# Control_Board.net
KiCad netlist of a schematic drawn in EAGLE
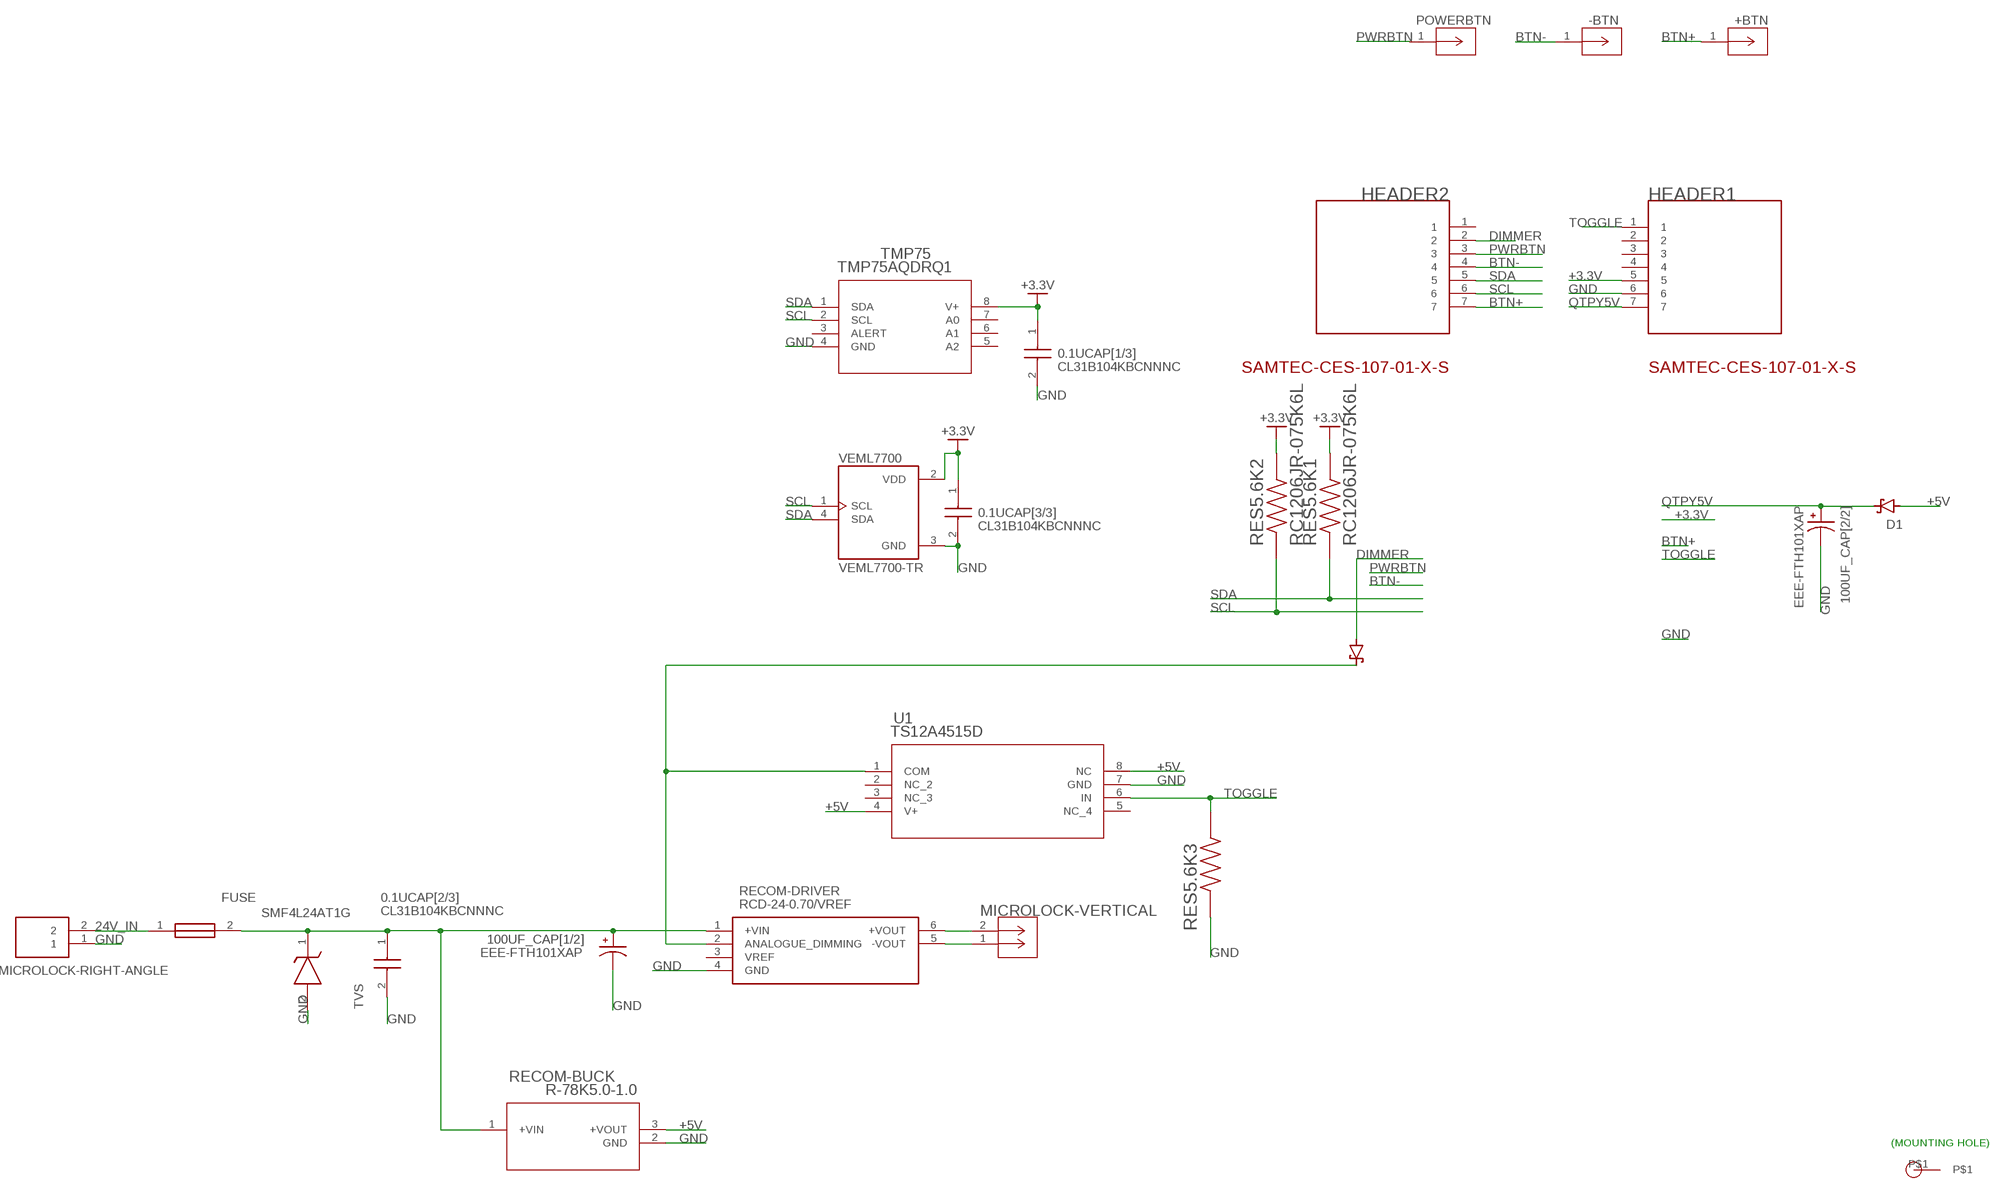
[diagram p0: schematic, sheet 1]

(export (version "E")
  (design (tool "Eeschema 10.0.6"))
  (components
    (comp (ref "+BTN")
      (value "807-22-001-10-001101")
      (footprint "eagle-import:CONN_807-22-001-10-001101_MIM")
      (fields (field (name "MANUFACTURER") "Mill-Max") (field (name "MPN") "807-22-001-10-001101"))
      (libsource (lib "eagle-import") (part "807-22-001-10-001101CONN_807-22-001-10-001101_MIM"))
    )
    (comp (ref "-BTN")
      (value "807-22-001-10-001101")
      (footprint "eagle-import:CONN_807-22-001-10-001101_MIM")
      (fields (field (name "MANUFACTURER") "Mill-Max") (field (name "MPN") "807-22-001-10-001101"))
      (libsource (lib "eagle-import") (part "807-22-001-10-001101CONN_807-22-001-10-001101_MIM"))
    )
    (comp (ref "0.1UCAP[1/3]")
      (value "CL31B104KBCNNNC")
      (footprint "eagle-import:CAPC3216X100N")
      (fields
        (field (name "MANUFACTURER") "Samsung Electro-Mechanics")
        (field (name "MPN") "CL31B104KBCNNNC")
      )
      (libsource (lib "eagle-import") (part "CL31B104KBCNNNC"))
    )
    (comp (ref "0.1UCAP[2/3]")
      (value "CL31B104KBCNNNC")
      (footprint "eagle-import:CAPC3216X100N")
      (fields
        (field (name "MANUFACTURER") "Samsung Electro-Mechanics")
        (field (name "MPN") "CL31B104KBCNNNC")
      )
      (libsource (lib "eagle-import") (part "CL31B104KBCNNNC"))
    )
    (comp (ref "0.1UCAP[3/3]")
      (value "CL31B104KBCNNNC")
      (footprint "eagle-import:CAPC3216X100N")
      (fields
        (field (name "MANUFACTURER") "Samsung Electro-Mechanics")
        (field (name "MPN") "CL31B104KBCNNNC")
      )
      (libsource (lib "eagle-import") (part "CL31B104KBCNNNC"))
    )
    (comp (ref "100UF_CAP[1/2]")
      (value "EEE-FTH101XAP")
      (footprint "eagle-import:CAP_EEEFTH101XAP")
      (fields (field (name "MANUFACTURER") "Panasonic") (field (name "MPN") "EEE-FTH101XAP"))
      (libsource (lib "eagle-import") (part "EEEFTH101XAP"))
    )
    (comp (ref "100UF_CAP[2/2]")
      (value "EEE-FTH101XAP")
      (footprint "eagle-import:CAP_EEEFTH101XAP")
      (fields (field (name "MANUFACTURER") "Panasonic") (field (name "MPN") "EEE-FTH101XAP"))
      (libsource (lib "eagle-import") (part "EEEFTH101XAP"))
    )
    (comp (ref "D1")
      (value "PMEG4010EGWX")
      (footprint "eagle-import:SOD-123")
      (fields (field (name "MANUFACTURER") "Nexperia") (field (name "MPN") "PMEG4010EGWX"))
      (libsource (lib "eagle-import") (part "PMEG4010EGWX"))
    )
    (comp (ref "D3")
      (value "PMEG4010EGWX")
      (footprint "eagle-import:SOD-123")
      (fields (field (name "MANUFACTURER") "Nexperia") (field (name "MPN") "PMEG4010EGWX"))
      (libsource (lib "eagle-import") (part "PMEG4010EGWX"))
    )
    (comp (ref "FUSE")
      (value "SMD2016B100TF/33")
      (footprint "eagle-import:SMD2016B100TF_33")
      (fields (field (name "MANUFACTURER") "YAGEO") (field (name "MPN") "SMD2016B100TF/33"))
      (libsource (lib "eagle-import") (part "SMD2016B100TF/33"))
    )
    (comp (ref "HEADER1")
      (value "CES-107-01-G-S")
      (footprint "eagle-import:SAMTEC-CES-107-01-X-S")
      (fields (field (name "MANUFACTURER") "Samtec"))
      (libsource (lib "eagle-import") (part "SAMTEC-CES-107-01-X-SJ"))
    )
    (comp (ref "HEADER2")
      (value "CES-107-01-G-S")
      (footprint "eagle-import:SAMTEC-CES-107-01-X-S")
      (fields (field (name "MANUFACTURER") "Samtec"))
      (libsource (lib "eagle-import") (part "SAMTEC-CES-107-01-X-SJ"))
    )
    (comp (ref "MICROLOCK-RIGHT-ANGLE")
      (value "2200980271")
      (footprint "eagle-import:2200980271")
      (fields (field (name "MANUFACTURER") "Molex") (field (name "MPN") "2200980271"))
      (libsource (lib "eagle-import") (part "220098-0271"))
    )
    (comp (ref "MICROLOCK-VERTICAL")
      (value "2200970271")
      (footprint "eagle-import:CONN_2200970000-SD_02_MOL")
      (fields (field (name "MANUFACTURER") "Molex") (field (name "MPN") "2200970271"))
      (libsource (lib "eagle-import") (part "2200970271CONN_2200970000-SD_02_MOL"))
    )
    (comp (ref "POWERBTN")
      (value "807-22-001-10-001101")
      (footprint "eagle-import:CONN_807-22-001-10-001101_MIM")
      (fields (field (name "MANUFACTURER") "Mill-Max") (field (name "MPN") "807-22-001-10-001101"))
      (libsource (lib "eagle-import") (part "807-22-001-10-001101CONN_807-22-001-10-001101_MIM"))
    )
    (comp (ref "RECOM-BUCK")
      (value "R-78K5.0-1.0")
      (footprint "eagle-import:R-78K5.0-1.0_RCP")
      (fields (field (name "MANUFACTURER") "RECOM Power") (field (name "MPN") "R-78K5.0-1.0"))
      (libsource (lib "eagle-import") (part "R-78K5.0-1.0SIP3_R-78K-0.5_RCP"))
    )
    (comp (ref "RECOM-DRIVER")
      (value "RCD-24-0.70/VREF")
      (footprint "eagle-import:RCD24030")
      (fields
        (field (name "MANUFACTURER") "RECOM Power")
        (field (name "MPN") "RCD-24-0.70/Vref")
        (field (name "MPN_1") "RCD-24-0.70/VREF")
      )
      (libsource (lib "eagle-import") (part "RCD-24-0.70_VREF"))
    )
    (comp (ref "RES5.6K1")
      (value "RC1206JR-075K6L")
      (footprint "eagle-import:RESC3116X65N")
      (fields (field (name "MANUFACTURER") "YAGEO") (field (name "MPN") "RC1206JR-075K6L"))
      (libsource (lib "eagle-import") (part "RC1206JR-075K6L"))
    )
    (comp (ref "RES5.6K2")
      (value "RC1206JR-075K6L")
      (footprint "eagle-import:RESC3116X65N")
      (fields (field (name "MANUFACTURER") "YAGEO") (field (name "MPN") "RC1206JR-075K6L"))
      (libsource (lib "eagle-import") (part "RC1206JR-075K6L"))
    )
    (comp (ref "RES5.6K3")
      (value "RC1206JR-075K6L")
      (footprint "eagle-import:RESC3116X65N")
      (fields (field (name "MANUFACTURER") "YAGEO") (field (name "MPN") "RC1206JR-075K6L"))
      (libsource (lib "eagle-import") (part "RC1206JR-075K6L"))
    )
    (comp (ref "TMP75")
      (value "TMP75AQDRQ1")
      (footprint "eagle-import:D8_TEX")
      (fields (field (name "MANUFACTURER") "Texas Instruments") (field (name "MPN") "TMP75AQDRQ1"))
      (libsource (lib "eagle-import") (part "TMP75AQDRQ1D8_TEX"))
    )
    (comp (ref "TVS")
      (value "SMF4L24AT1G")
      (footprint "eagle-import:SODFL3619X98N")
      (fields (field (name "MANUFACTURER") "Littelfuse"))
      (libsource (lib "eagle-import") (part "SMF4L24AT1G"))
    )
    (comp (ref "U$2")
      (value "2.5MMPLATEDTHROUGHHOLE")
      (footprint "eagle-import:2.5MMPLATEDHOLE")
      (libsource (lib "eagle-import") (part "2.5MMPLATEDTHROUGHHOLE"))
    )
    (comp (ref "U1")
      (value "TS12A4515D")
      (footprint "eagle-import:D8-L")
      (fields (field (name "MANUFACTURER") "Texas Instruments") (field (name "MPN") "TS12A4515D"))
      (libsource (lib "eagle-import") (part "TS12A4515DD8-L"))
    )
    (comp (ref "VEML7700")
      (value "VEML7700-TR")
      (footprint "eagle-import:XDCR_VEML7700-TR")
      (fields (field (name "MANUFACTURER") "Vishay") (field (name "MPN") "VEML7700-TR"))
      (libsource (lib "eagle-import") (part "VEML7700-TR"))
    )
  )
  (nets
    (net (code "1") (name "+3.3V") (class "Default")
      (node (ref "0.1UCAP[1/3]") (pin "1") (pinfunction "1_1") (pintype "bidirectional"))
      (node (ref "0.1UCAP[3/3]") (pin "1") (pinfunction "1_1") (pintype "bidirectional"))
      (node (ref "HEADER1") (pin "5") (pinfunction "5_5") (pintype "bidirectional"))
      (node (ref "RES5.6K1") (pin "2") (pinfunction "2_2") (pintype "passive"))
      (node (ref "RES5.6K2") (pin "2") (pinfunction "2_2") (pintype "passive"))
      (node (ref "TMP75") (pin "8") (pinfunction "V+_8") (pintype "power_in"))
      (node (ref "VEML7700") (pin "2") (pinfunction "VDD_2") (pintype "power_in"))
    )
    (net (code "2") (name "/+5V") (class "Default")
      (node (ref "D1") (pin "A") (pinfunction "A_A") (pintype "passive"))
      (node (ref "RECOM-BUCK") (pin "3") (pinfunction "+VOUT_3") (pintype "output"))
      (node (ref "U1") (pin "4") (pinfunction "V+_4") (pintype "power_in"))
      (node (ref "U1") (pin "8") (pinfunction "NC_8") (pintype "passive"))
    )
    (net (code "3") (name "/24V_IN") (class "Default")
      (node (ref "FUSE") (pin "1") (pinfunction "1_1") (pintype "bidirectional"))
      (node (ref "MICROLOCK-RIGHT-ANGLE") (pin "2") (pinfunction "2_2") (pintype "bidirectional"))
    )
    (net (code "4") (name "/BTN+") (class "Default")
      (node (ref "+BTN") (pin "1") (pinfunction "1_1") (pintype "passive"))
      (node (ref "HEADER2") (pin "7") (pinfunction "7_7") (pintype "bidirectional"))
    )
    (net (code "5") (name "/BTN-") (class "Default")
      (node (ref "-BTN") (pin "1") (pinfunction "1_1") (pintype "passive"))
      (node (ref "HEADER2") (pin "4") (pinfunction "4_4") (pintype "bidirectional"))
    )
    (net (code "6") (name "/DIMMER") (class "Default")
      (node (ref "D3") (pin "A") (pinfunction "A_A") (pintype "passive"))
      (node (ref "HEADER2") (pin "2") (pinfunction "2_2") (pintype "bidirectional"))
    )
    (net (code "7") (name "/GND") (class "Default")
      (node (ref "0.1UCAP[1/3]") (pin "2") (pinfunction "2_2") (pintype "bidirectional"))
      (node (ref "0.1UCAP[2/3]") (pin "2") (pinfunction "2_2") (pintype "bidirectional"))
      (node (ref "0.1UCAP[3/3]") (pin "2") (pinfunction "2_2") (pintype "bidirectional"))
      (node (ref "100UF_CAP[1/2]") (pin "2") (pinfunction "2_2") (pintype "passive"))
      (node (ref "100UF_CAP[2/2]") (pin "2") (pinfunction "2_2") (pintype "passive"))
      (node (ref "HEADER1") (pin "6") (pinfunction "6_6") (pintype "bidirectional"))
      (node (ref "MICROLOCK-RIGHT-ANGLE") (pin "1") (pinfunction "1_1") (pintype "bidirectional"))
      (node (ref "RECOM-BUCK") (pin "2") (pinfunction "GND_2") (pintype "passive"))
      (node (ref "RECOM-DRIVER") (pin "4") (pinfunction "GND_4") (pintype "bidirectional"))
      (node (ref "RES5.6K3") (pin "1") (pinfunction "1_1") (pintype "passive"))
      (node (ref "TMP75") (pin "4") (pinfunction "GND_4") (pintype "power_in"))
      (node (ref "TVS") (pin "2") (pinfunction "A_2") (pintype "bidirectional"))
      (node (ref "U1") (pin "7") (pinfunction "GND_7") (pintype "power_in"))
      (node (ref "VEML7700") (pin "3") (pinfunction "GND_3") (pintype "power_in"))
    )
    (net (code "8") (name "/PWRBTN") (class "Default")
      (node (ref "HEADER2") (pin "3") (pinfunction "3_3") (pintype "bidirectional"))
      (node (ref "POWERBTN") (pin "1") (pinfunction "1_1") (pintype "passive"))
    )
    (net (code "9") (name "/QTPY5V") (class "Default")
      (node (ref "100UF_CAP[2/2]") (pin "1") (pinfunction "1_1") (pintype "passive"))
      (node (ref "D1") (pin "C") (pinfunction "C_C") (pintype "passive"))
      (node (ref "HEADER1") (pin "7") (pinfunction "7_7") (pintype "bidirectional"))
    )
    (net (code "10") (name "/SCL") (class "Default")
      (node (ref "HEADER2") (pin "6") (pinfunction "6_6") (pintype "bidirectional"))
      (node (ref "RES5.6K2") (pin "1") (pinfunction "1_1") (pintype "passive"))
      (node (ref "TMP75") (pin "2") (pinfunction "SCL_2") (pintype "passive"))
      (node (ref "VEML7700") (pin "1") (pinfunction "SCL_1") (pintype "input"))
    )
    (net (code "11") (name "/SDA") (class "Default")
      (node (ref "HEADER2") (pin "5") (pinfunction "5_5") (pintype "bidirectional"))
      (node (ref "RES5.6K1") (pin "1") (pinfunction "1_1") (pintype "passive"))
      (node (ref "TMP75") (pin "1") (pinfunction "SDA_1") (pintype "passive"))
      (node (ref "VEML7700") (pin "4") (pinfunction "SDA_4") (pintype "bidirectional"))
    )
    (net (code "12") (name "/TOGGLE") (class "Default")
      (node (ref "HEADER1") (pin "1") (pinfunction "1_1") (pintype "bidirectional"))
      (node (ref "RES5.6K3") (pin "2") (pinfunction "2_2") (pintype "passive"))
      (node (ref "U1") (pin "6") (pinfunction "IN_6") (pintype "input"))
    )
    (net (code "13") (name "Net-(MICROLOCK-VERTICAL-1)") (class "Default")
      (node (ref "MICROLOCK-VERTICAL") (pin "2") (pinfunction "1_2") (pintype "passive"))
      (node (ref "RECOM-DRIVER") (pin "6") (pinfunction "+VOUT_6") (pintype "bidirectional"))
    )
    (net (code "14") (name "Net-(MICROLOCK-VERTICAL-2)") (class "Default")
      (node (ref "MICROLOCK-VERTICAL") (pin "1") (pinfunction "2_1") (pintype "passive"))
      (node (ref "RECOM-DRIVER") (pin "5") (pinfunction "-VOUT_5") (pintype "bidirectional"))
    )
    (net (code "15") (name "Net-(RECOM-BUCK-+VIN)") (class "Default")
      (node (ref "0.1UCAP[2/3]") (pin "1") (pinfunction "1_1") (pintype "bidirectional"))
      (node (ref "100UF_CAP[1/2]") (pin "1") (pinfunction "1_1") (pintype "passive"))
      (node (ref "FUSE") (pin "2") (pinfunction "2_2") (pintype "bidirectional"))
      (node (ref "RECOM-BUCK") (pin "1") (pinfunction "+VIN_1") (pintype "power_in"))
      (node (ref "RECOM-DRIVER") (pin "1") (pinfunction "+VIN_1") (pintype "bidirectional"))
      (node (ref "TVS") (pin "1") (pinfunction "K_1") (pintype "bidirectional"))
    )
    (net (code "16") (name "Net-(RECOM-DRIVER-ANALOGUE_DIMMING)") (class "Default")
      (node (ref "D3") (pin "C") (pinfunction "C_C") (pintype "passive"))
      (node (ref "RECOM-DRIVER") (pin "2") (pinfunction "ANALOGUE_DIMMING_2") (pintype "bidirectional"))
      (node (ref "U1") (pin "1") (pinfunction "COM_1") (pintype "passive"))
    )
    (net (code "17") (name "unconnected-(HEADER1-Pad2)") (class "Default")
      (node (ref "HEADER1") (pin "2") (pinfunction "2_2") (pintype "bidirectional"))
    )
    (net (code "18") (name "unconnected-(HEADER1-Pad3)") (class "Default")
      (node (ref "HEADER1") (pin "3") (pinfunction "3_3") (pintype "bidirectional"))
    )
    (net (code "19") (name "unconnected-(HEADER1-Pad4)") (class "Default")
      (node (ref "HEADER1") (pin "4") (pinfunction "4_4") (pintype "bidirectional"))
    )
    (net (code "20") (name "unconnected-(HEADER2-Pad1)") (class "Default")
      (node (ref "HEADER2") (pin "1") (pinfunction "1_1") (pintype "bidirectional"))
    )
    (net (code "21") (name "unconnected-(RECOM-DRIVER-VREF-Pad3)") (class "Default")
      (node (ref "RECOM-DRIVER") (pin "3") (pinfunction "VREF_3") (pintype "bidirectional"))
    )
    (net (code "22") (name "unconnected-(TMP75-A0-Pad7)") (class "Default")
      (node (ref "TMP75") (pin "7") (pinfunction "A0_7") (pintype "passive"))
    )
    (net (code "23") (name "unconnected-(TMP75-A1-Pad6)") (class "Default")
      (node (ref "TMP75") (pin "6") (pinfunction "A1_6") (pintype "passive"))
    )
    (net (code "24") (name "unconnected-(TMP75-A2-Pad5)") (class "Default")
      (node (ref "TMP75") (pin "5") (pinfunction "A2_5") (pintype "passive"))
    )
    (net (code "25") (name "unconnected-(TMP75-ALERT-Pad3)") (class "Default")
      (node (ref "TMP75") (pin "3") (pinfunction "ALERT_3") (pintype "passive"))
    )
    (net (code "26") (name "unconnected-(U$2-PadP$1)") (class "Default")
      (node (ref "U$2") (pin "P$1") (pinfunction "P$1_P$1") (pintype "passive"))
    )
    (net (code "27") (name "unconnected-(U1-NC_2-Pad2)") (class "Default")
      (node (ref "U1") (pin "2") (pinfunction "NC_2_2") (pintype "passive"))
    )
    (net (code "28") (name "unconnected-(U1-NC_3-Pad3)") (class "Default")
      (node (ref "U1") (pin "3") (pinfunction "NC_3_3") (pintype "passive"))
    )
    (net (code "29") (name "unconnected-(U1-NC_4-Pad5)") (class "Default")
      (node (ref "U1") (pin "5") (pinfunction "NC_4_5") (pintype "passive"))
    )
  )
)
